# Input.net
KiCad netlist of a schematic drawn in Altium Designer
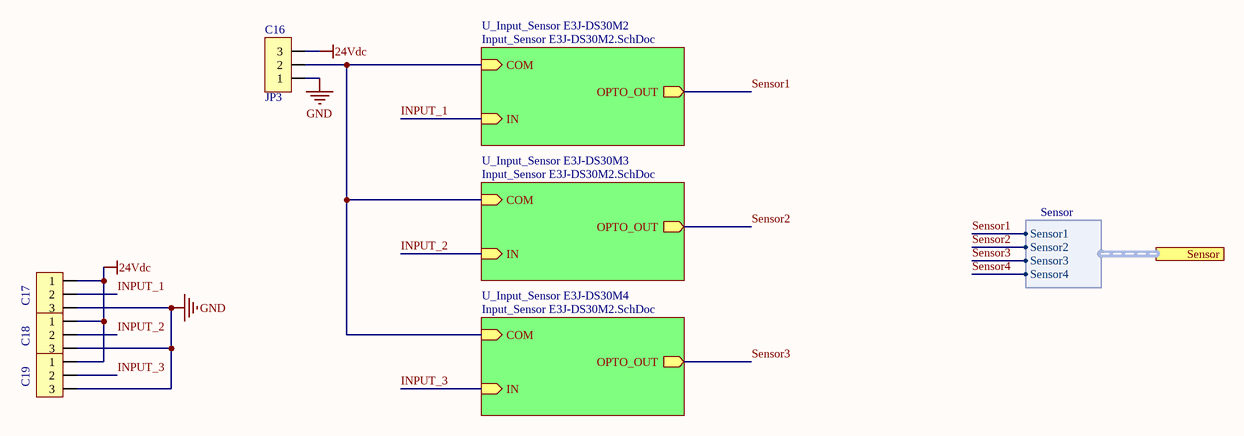
[diagram p0: Input.SchDoc]

(export (version "E")
  (design (tool "Eeschema 10.0.6"))
  (components
    (comp (ref "C16")
      (value "JP3")
      (footprint "JP3-CLOSED")
      (description "WR-PHD 2.54 mm Angled Socket Header")
      (fields
        (field (name "MANUFACTURER") "Würth Elektronik eiSos GmbH")
        (field (name "PARTNO") "613003143121")
        (field (name "CREATED BY") "Karrer Zheng")
      )
      (libsource (lib "thu vien 3d") (part "JP3"))
    )
    (comp (ref "C17")
      (value "Header3")
      (footprint "Header3 90")
      (description "Header IDC, 3 x 1 Pin Vertical 2.54mm Pitch (Non-Boxed, Male)")
      (fields
        (field (name "MANUFACTURER") "Würth Elektronik eiSos GmbH")
        (field (name "PARTNO") "613002143121")
        (field (name "CREATED BY") "Karrer Zheng")
      )
      (libsource (lib "thu vien 3d") (part "Header3"))
    )
    (comp (ref "C18")
      (value "Header3")
      (footprint "Header3 90")
      (description "Header IDC, 3 x 1 Pin Vertical 2.54mm Pitch (Non-Boxed, Male)")
      (fields
        (field (name "MANUFACTURER") "Würth Elektronik eiSos GmbH")
        (field (name "PARTNO") "613002143121")
        (field (name "CREATED BY") "Karrer Zheng")
      )
      (libsource (lib "thu vien 3d") (part "Header3"))
    )
    (comp (ref "C19")
      (value "Header3")
      (footprint "Header3 90")
      (description "Header IDC, 3 x 1 Pin Vertical 2.54mm Pitch (Non-Boxed, Male)")
      (fields
        (field (name "MANUFACTURER") "Würth Elektronik eiSos GmbH")
        (field (name "PARTNO") "613002143121")
        (field (name "CREATED BY") "Karrer Zheng")
      )
      (libsource (lib "thu vien 3d") (part "Header3"))
    )
  )
  (nets
    (net (code "2") (name "/COM") (class "Default")
      (node (ref "C16") (pin "2") (pinfunction "2_2") (pintype "passive"))
    )
    (net (code "3") (name "/INPUT_1") (class "Default")
      (node (ref "C17") (pin "2") (pinfunction "2_2") (pintype "passive"))
    )
    (net (code "4") (name "/INPUT_2") (class "Default")
      (node (ref "C18") (pin "2") (pinfunction "2_2") (pintype "passive"))
    )
    (net (code "5") (name "/INPUT_3") (class "Default")
      (node (ref "C19") (pin "2") (pinfunction "2_2") (pintype "passive"))
    )
    (net (code "11") (name "24Vdc") (class "Default")
      (node (ref "C16") (pin "3") (pinfunction "3_3") (pintype "passive"))
      (node (ref "C17") (pin "1") (pinfunction "1_1") (pintype "passive"))
      (node (ref "C18") (pin "1") (pinfunction "1_1") (pintype "passive"))
      (node (ref "C19") (pin "1") (pinfunction "1_1") (pintype "passive"))
    )
    (net (code "12") (name "GND") (class "Default")
      (node (ref "C16") (pin "1") (pinfunction "1_1") (pintype "passive"))
      (node (ref "C17") (pin "3") (pinfunction "3_3") (pintype "passive"))
      (node (ref "C18") (pin "3") (pinfunction "3_3") (pintype "passive"))
      (node (ref "C19") (pin "3") (pinfunction "3_3") (pintype "passive"))
    )
  )
)
